# IPM.net
KiCad netlist of a schematic drawn in EasyEDA Pro
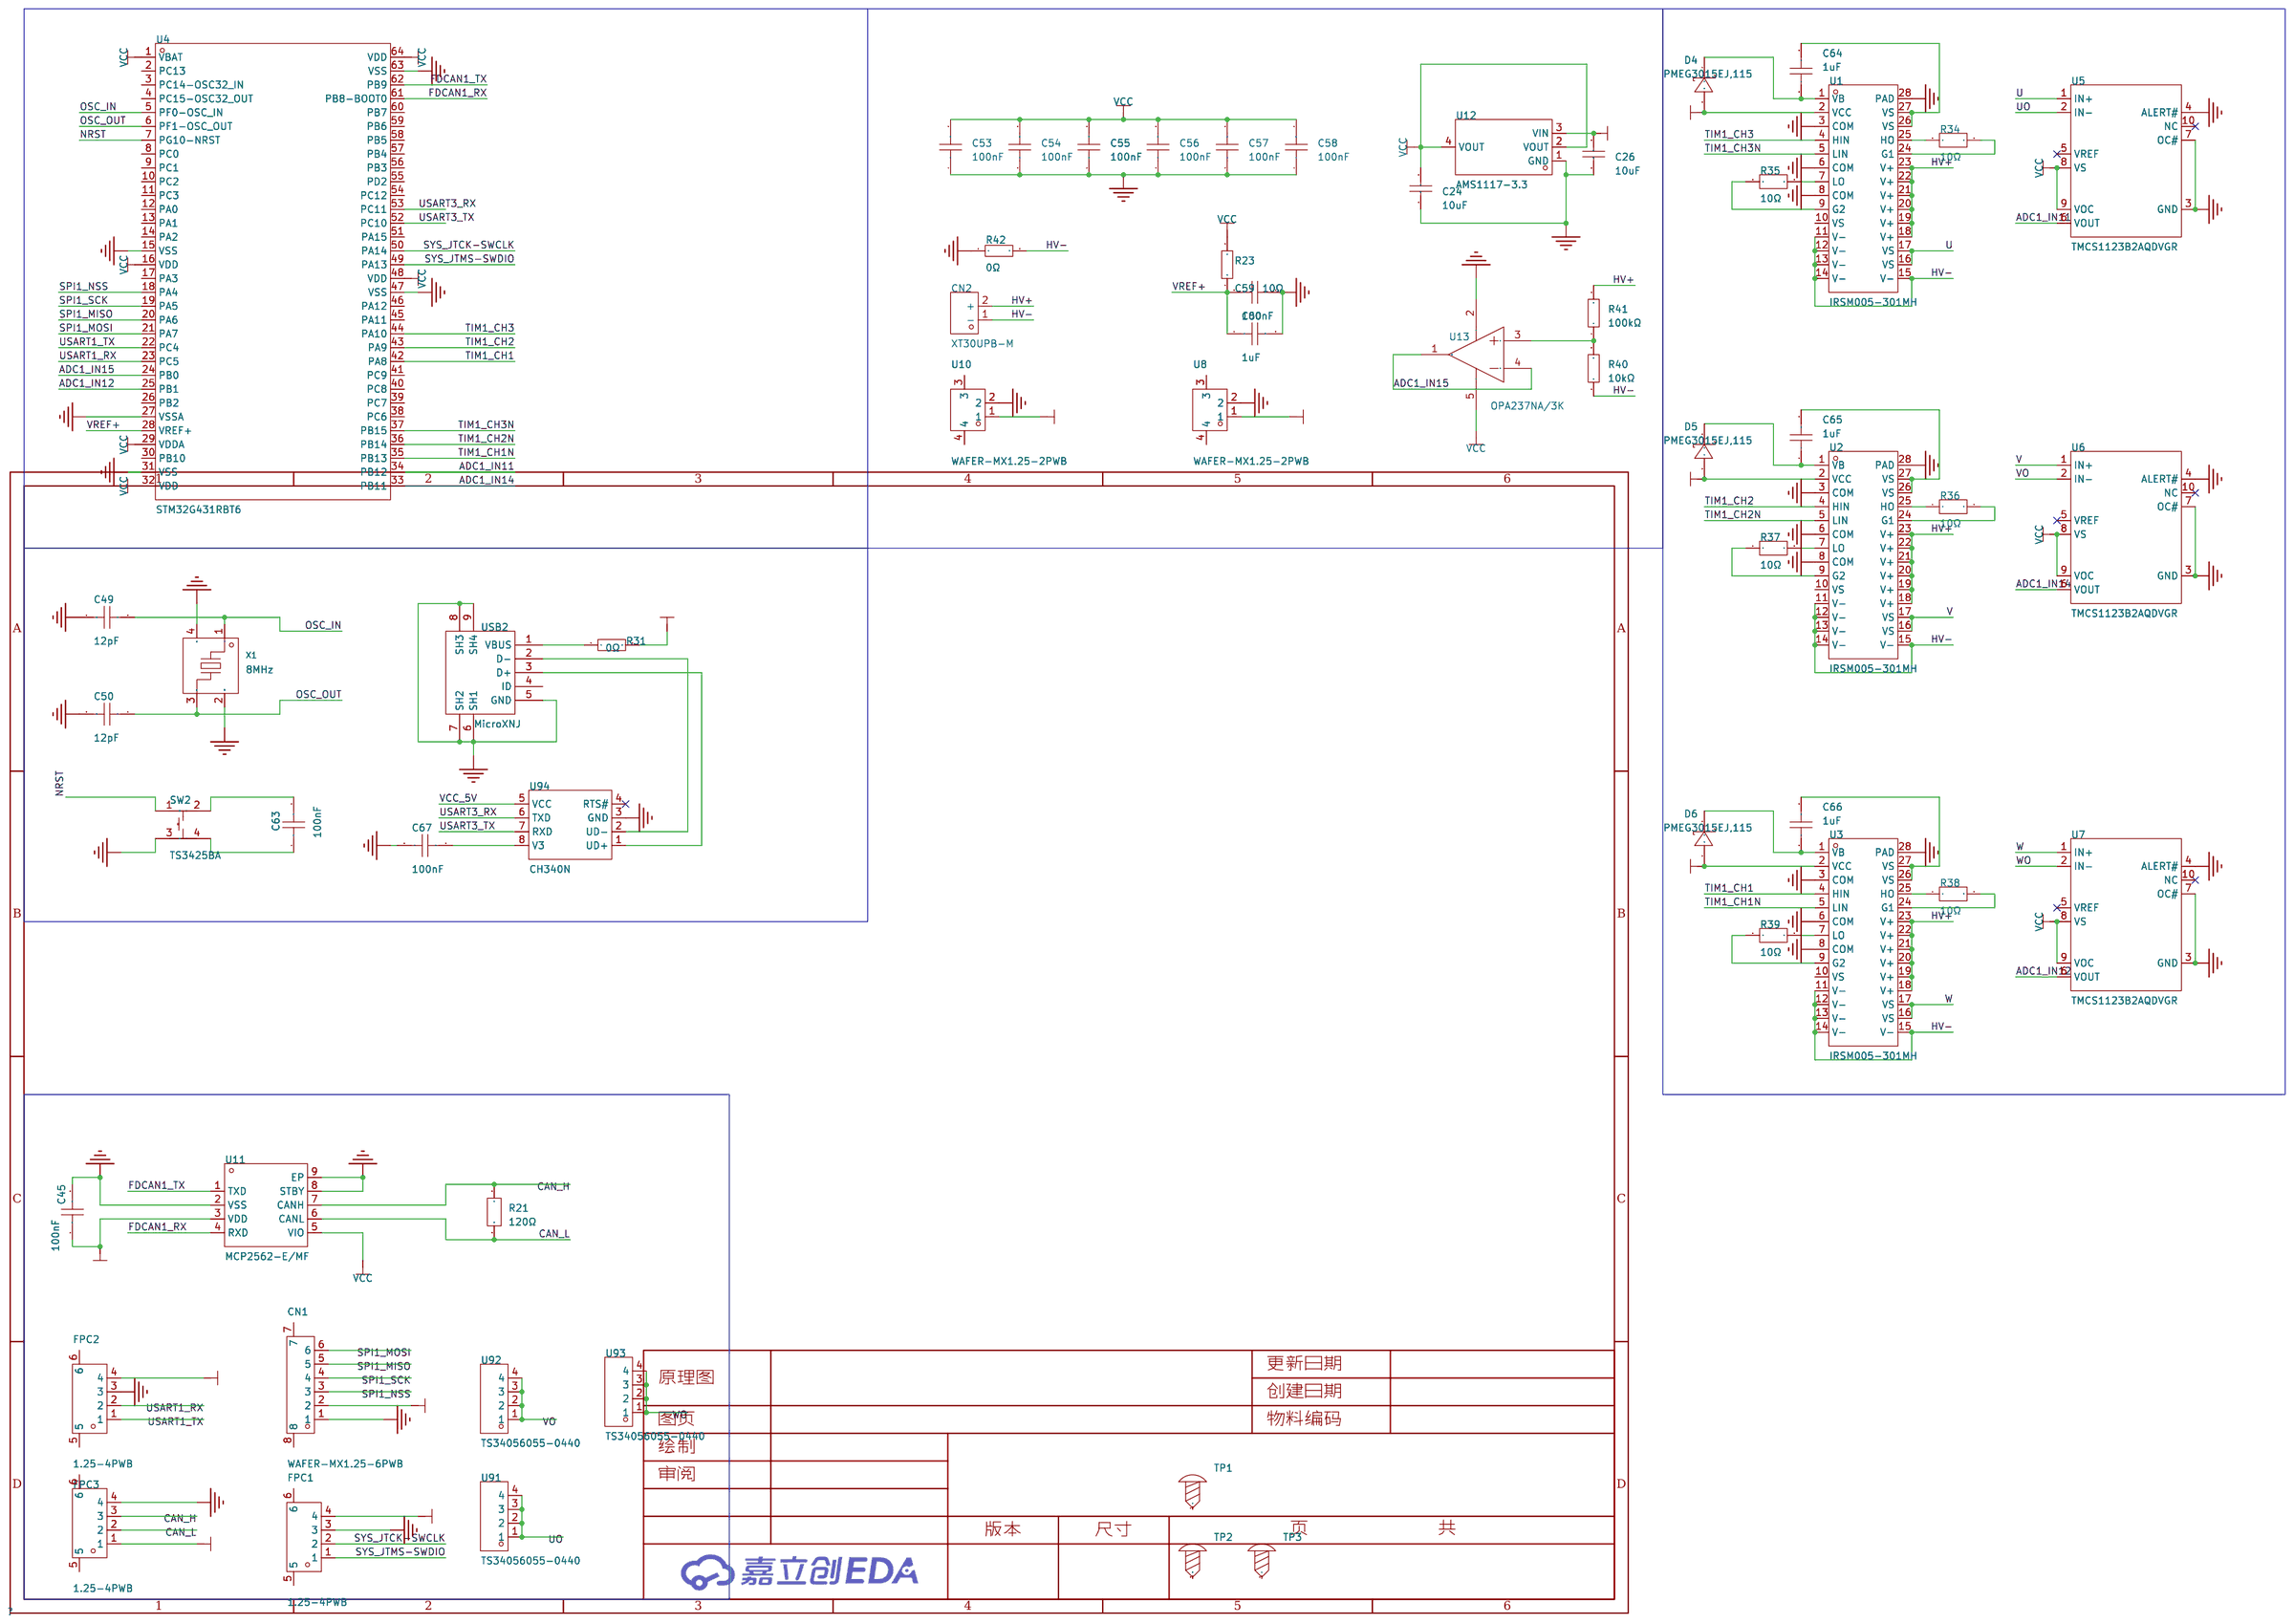
[diagram p0: schematic sheet]

(export (version "E")
  (design (tool "Eeschema 10.0.6"))
  (components
    (comp (ref "C24")
      (value "10uF")
      (footprint "easyedapro:C0603")
      (description "容值:10uF;精度:±10%;额定电压:10V;材质(温度系数):X5R;")
      (fields (field (name "Manufacturer Part") "0603X106K100") (field (name "Manufacturer") "Walsin(华新科)"))
      (libsource (lib "easyedapro") (part "0603X106K100"))
    )
    (comp (ref "C26")
      (value "10uF")
      (footprint "easyedapro:C0603")
      (description "容值:10uF;精度:±10%;额定电压:10V;材质(温度系数):X5R;")
      (fields (field (name "Manufacturer Part") "0603X106K100") (field (name "Manufacturer") "Walsin(华新科)"))
      (libsource (lib "easyedapro") (part "0603X106K100"))
    )
    (comp (ref "C45")
      (value "100nF")
      (footprint "easyedapro:C0603")
      (description "容值:100nF;精度:±10%;额定电压:50V;材质(温度系数):X7R;")
      (fields
        (field (name "Manufacturer Part") "CC0603KRX7R9BB104")
        (field (name "Manufacturer") "YAGEO(国巨)")
      )
      (libsource (lib "easyedapro") (part "CC0603KRX7R9BB104"))
    )
    (comp (ref "C49")
      (value "12pF")
      (footprint "easyedapro:C0603")
      (description "容值:12pF;精度:±1%;额定电压:50V;材质(温度系数):NP0;")
      (fields
        (field (name "Manufacturer Part") "CC0603FRNPO9BN120")
        (field (name "Manufacturer") "YAGEO(国巨)")
      )
      (libsource (lib "easyedapro") (part "CC0603FRNPO9BN120"))
    )
    (comp (ref "C50")
      (value "12pF")
      (footprint "easyedapro:C0603")
      (description "容值:12pF;精度:±1%;额定电压:50V;材质(温度系数):NP0;")
      (fields
        (field (name "Manufacturer Part") "CC0603FRNPO9BN120")
        (field (name "Manufacturer") "YAGEO(国巨)")
      )
      (libsource (lib "easyedapro") (part "CC0603FRNPO9BN120"))
    )
    (comp (ref "C53")
      (value "100nF")
      (footprint "easyedapro:C0603")
      (description "容值:100nF;精度:±10%;额定电压:50V;材质(温度系数):X7R;")
      (fields
        (field (name "Manufacturer Part") "CC0603KRX7R9BB104")
        (field (name "Manufacturer") "YAGEO(国巨)")
      )
      (libsource (lib "easyedapro") (part "CC0603KRX7R9BB104"))
    )
    (comp (ref "C54")
      (value "100nF")
      (footprint "easyedapro:C0603")
      (description "容值:100nF;精度:±10%;额定电压:50V;材质(温度系数):X7R;")
      (fields
        (field (name "Manufacturer Part") "CC0603KRX7R9BB104")
        (field (name "Manufacturer") "YAGEO(国巨)")
      )
      (libsource (lib "easyedapro") (part "CC0603KRX7R9BB104"))
    )
    (comp (ref "C55")
      (value "100nF")
      (footprint "easyedapro:C0603")
      (description "容值:100nF;精度:±10%;额定电压:50V;材质(温度系数):X7R;")
      (fields
        (field (name "Manufacturer Part") "CC0603KRX7R9BB104")
        (field (name "Manufacturer") "YAGEO(国巨)")
      )
      (libsource (lib "easyedapro") (part "CC0603KRX7R9BB104"))
    )
    (comp (ref "C56")
      (value "100nF")
      (footprint "easyedapro:C0603")
      (description "容值:100nF;精度:±10%;额定电压:50V;材质(温度系数):X7R;")
      (fields
        (field (name "Manufacturer Part") "CC0603KRX7R9BB104")
        (field (name "Manufacturer") "YAGEO(国巨)")
      )
      (libsource (lib "easyedapro") (part "CC0603KRX7R9BB104"))
    )
    (comp (ref "C57")
      (value "100nF")
      (footprint "easyedapro:C0603")
      (description "容值:100nF;精度:±10%;额定电压:50V;材质(温度系数):X7R;")
      (fields
        (field (name "Manufacturer Part") "CC0603KRX7R9BB104")
        (field (name "Manufacturer") "YAGEO(国巨)")
      )
      (libsource (lib "easyedapro") (part "CC0603KRX7R9BB104"))
    )
    (comp (ref "C58")
      (value "100nF")
      (footprint "easyedapro:C0603")
      (description "容值:100nF;精度:±10%;额定电压:50V;材质(温度系数):X7R;")
      (fields
        (field (name "Manufacturer Part") "CC0603KRX7R9BB104")
        (field (name "Manufacturer") "YAGEO(国巨)")
      )
      (libsource (lib "easyedapro") (part "CC0603KRX7R9BB104"))
    )
    (comp (ref "C59")
      (value "100nF")
      (footprint "easyedapro:C0603")
      (description "容值:100nF;精度:±10%;额定电压:50V;材质(温度系数):X7R;")
      (fields
        (field (name "Manufacturer Part") "CC0603KRX7R9BB104")
        (field (name "Manufacturer") "YAGEO(国巨)")
      )
      (libsource (lib "easyedapro") (part "CC0603KRX7R9BB104"))
    )
    (comp (ref "C60")
      (value "1uF")
      (footprint "easyedapro:C0603")
      (description "容值:1uF;精度:±5%;额定电压:10V;材质(温度系数):X7R;")
      (fields
        (field (name "Manufacturer Part") "CC0603JRX7R6BB105")
        (field (name "Manufacturer") "YAGEO(国巨)")
      )
      (libsource (lib "easyedapro") (part "CC0603JRX7R6BB105"))
    )
    (comp (ref "C63")
      (value "100nF")
      (footprint "easyedapro:C0603")
      (description "容值:100nF;精度:±10%;额定电压:50V;材质(温度系数):X7R;")
      (fields
        (field (name "Manufacturer Part") "CC0603KRX7R9BB104")
        (field (name "Manufacturer") "YAGEO(国巨)")
      )
      (libsource (lib "easyedapro") (part "CC0603KRX7R9BB104"))
    )
    (comp (ref "C64")
      (value "1uF")
      (footprint "easyedapro:C0603")
      (description "容值:1uF;精度:±10%;额定电压:50V;温度系数:X5R;")
      (fields
        (field (name "Manufacturer Part") "CL10A105KB8NNNC")
        (field (name "Manufacturer") "SAMSUNG(三星)")
      )
      (libsource (lib "easyedapro") (part "CL10A105KB8NNNC"))
    )
    (comp (ref "C65")
      (value "1uF")
      (footprint "easyedapro:C0603")
      (description "容值:1uF;精度:±10%;额定电压:50V;温度系数:X5R;")
      (fields
        (field (name "Manufacturer Part") "CL10A105KB8NNNC")
        (field (name "Manufacturer") "SAMSUNG(三星)")
      )
      (libsource (lib "easyedapro") (part "CL10A105KB8NNNC"))
    )
    (comp (ref "C66")
      (value "1uF")
      (footprint "easyedapro:C0603")
      (description "容值:1uF;精度:±10%;额定电压:50V;温度系数:X5R;")
      (fields
        (field (name "Manufacturer Part") "CL10A105KB8NNNC")
        (field (name "Manufacturer") "SAMSUNG(三星)")
      )
      (libsource (lib "easyedapro") (part "CL10A105KB8NNNC"))
    )
    (comp (ref "C67")
      (value "100nF")
      (footprint "easyedapro:C0603")
      (description "容值:100nF;精度:±10%;额定电压:50V;温度系数:X7R;")
      (fields
        (field (name "Manufacturer Part") "FCC0603B104K500CT")
        (field (name "Manufacturer") "FOJAN(富捷)")
      )
      (libsource (lib "easyedapro") (part "FCC0603B104K500CT"))
    )
    (comp (ref "CN1")
      (value "WAFER-MX1.25-6PWB")
      (footprint "easyedapro:CONN-SMD_6P-P1.25_XUNPU_WAFER-MX1.25-6PWB")
      (fields (field (name "Manufacturer") "XUNPU(讯普)"))
      (libsource (lib "easyedapro") (part "WAFER-MX1.25-6PWB"))
    )
    (comp (ref "CN2")
      (value "XT30UPB-M")
      (footprint "easyedapro:CONN-TH_XT30UPB-M")
      (description "类别:-;类型1:-;")
      (fields (field (name "Manufacturer") "AMASS(艾迈斯)"))
      (libsource (lib "easyedapro") (part "XT30UPB-M"))
    )
    (comp (ref "D4")
      (value "PMEG3015EJ,115")
      (footprint "easyedapro:SOD-323F_L1.7-W1.3-LS2.5-R-RD")
      (description "二极管配置:1个独立式;正向压降(Vf):550mV@1.5A;直流反向耐压(Vr):30V;整流电流:1.5A;")
      (fields (field (name "Manufacturer") "Nexperia(安世)"))
      (libsource (lib "easyedapro") (part "PMEG3015EJ,115"))
    )
    (comp (ref "D5")
      (value "PMEG3015EJ,115")
      (footprint "easyedapro:SOD-323F_L1.7-W1.3-LS2.5-R-RD")
      (description "二极管配置:1个独立式;正向压降(Vf):550mV@1.5A;直流反向耐压(Vr):30V;整流电流:1.5A;")
      (fields (field (name "Manufacturer") "Nexperia(安世)"))
      (libsource (lib "easyedapro") (part "PMEG3015EJ,115"))
    )
    (comp (ref "D6")
      (value "PMEG3015EJ,115")
      (footprint "easyedapro:SOD-323F_L1.7-W1.3-LS2.5-R-RD")
      (description "二极管配置:1个独立式;正向压降(Vf):550mV@1.5A;直流反向耐压(Vr):30V;整流电流:1.5A;")
      (fields (field (name "Manufacturer") "Nexperia(安世)"))
      (libsource (lib "easyedapro") (part "PMEG3015EJ,115"))
    )
    (comp (ref "FPC1")
      (value "1.25-4PWB")
      (footprint "easyedapro:CONN-SMD_1.25-4PWB")
      (fields (field (name "Manufacturer") "DEALON(德艺隆)"))
      (libsource (lib "easyedapro") (part "1.25-4PWB"))
    )
    (comp (ref "FPC2")
      (value "1.25-4PWB")
      (footprint "easyedapro:CONN-SMD_1.25-4PWB")
      (fields (field (name "Manufacturer") "DEALON(德艺隆)"))
      (libsource (lib "easyedapro") (part "1.25-4PWB"))
    )
    (comp (ref "FPC3")
      (value "1.25-4PWB")
      (footprint "easyedapro:CONN-SMD_1.25-4PWB")
      (fields (field (name "Manufacturer") "DEALON(德艺隆)"))
      (libsource (lib "easyedapro") (part "1.25-4PWB"))
    )
    (comp (ref "R21")
      (value "120Ω")
      (footprint "easyedapro:R0603")
      (description "电阻类型:薄膜电阻;阻值:120Ω;精度:±0.1%;功率:100mW;")
      (fields (field (name "Manufacturer Part") "AR03BTCX1200") (field (name "Manufacturer") "Viking(光颉)"))
      (libsource (lib "easyedapro") (part "AR03BTCX1200"))
    )
    (comp (ref "R23")
      (value "10Ω")
      (footprint "easyedapro:R0603")
      (description "电阻类型:厚膜电阻;阻值:10Ω;精度:±1%;功率:100mW;")
      (fields
        (field (name "Manufacturer Part") "0603WAF100JT5E")
        (field (name "Manufacturer") "UNI-ROYAL(厚声)")
      )
      (libsource (lib "easyedapro") (part "0603WAF100JT5E"))
    )
    (comp (ref "R31")
      (value "0Ω")
      (footprint "easyedapro:R0603")
      (description "电阻类型:厚膜电阻;阻值:0Ω;精度:±1%;功率:100mW;最大工作电压:75V;")
      (fields
        (field (name "Manufacturer Part") "0603WAF0000T5E")
        (field (name "Manufacturer") "UNI-ROYAL(厚声)")
      )
      (libsource (lib "easyedapro") (part "0603WAF0000T5E"))
    )
    (comp (ref "R34")
      (value "10Ω")
      (footprint "easyedapro:R0603")
      (description "电阻类型:陶瓷电阻;阻值:10Ω;精度:±0.1%;功率:100mW;温度系数:±25ppm/°C;")
      (fields
        (field (name "Manufacturer Part") "HoARG0603-1/10W-10R-0.1%-TCR25")
        (field (name "Manufacturer") "Milliohm(毫欧)")
      )
      (libsource (lib "easyedapro") (part "HOARG0603-1/10W-10R-0.1%-TCR25"))
    )
    (comp (ref "R35")
      (value "10Ω")
      (footprint "easyedapro:R0603")
      (description "电阻类型:陶瓷电阻;阻值:10Ω;精度:±0.1%;功率:100mW;温度系数:±25ppm/°C;")
      (fields
        (field (name "Manufacturer Part") "HoARG0603-1/10W-10R-0.1%-TCR25")
        (field (name "Manufacturer") "Milliohm(毫欧)")
      )
      (libsource (lib "easyedapro") (part "HOARG0603-1/10W-10R-0.1%-TCR25"))
    )
    (comp (ref "R36")
      (value "10Ω")
      (footprint "easyedapro:R0603")
      (description "电阻类型:陶瓷电阻;阻值:10Ω;精度:±0.1%;功率:100mW;温度系数:±25ppm/°C;")
      (fields
        (field (name "Manufacturer Part") "HoARG0603-1/10W-10R-0.1%-TCR25")
        (field (name "Manufacturer") "Milliohm(毫欧)")
      )
      (libsource (lib "easyedapro") (part "HOARG0603-1/10W-10R-0.1%-TCR25"))
    )
    (comp (ref "R37")
      (value "10Ω")
      (footprint "easyedapro:R0603")
      (description "电阻类型:陶瓷电阻;阻值:10Ω;精度:±0.1%;功率:100mW;温度系数:±25ppm/°C;")
      (fields
        (field (name "Manufacturer Part") "HoARG0603-1/10W-10R-0.1%-TCR25")
        (field (name "Manufacturer") "Milliohm(毫欧)")
      )
      (libsource (lib "easyedapro") (part "HOARG0603-1/10W-10R-0.1%-TCR25"))
    )
    (comp (ref "R38")
      (value "10Ω")
      (footprint "easyedapro:R0603")
      (description "电阻类型:陶瓷电阻;阻值:10Ω;精度:±0.1%;功率:100mW;温度系数:±25ppm/°C;")
      (fields
        (field (name "Manufacturer Part") "HoARG0603-1/10W-10R-0.1%-TCR25")
        (field (name "Manufacturer") "Milliohm(毫欧)")
      )
      (libsource (lib "easyedapro") (part "HOARG0603-1/10W-10R-0.1%-TCR25"))
    )
    (comp (ref "R39")
      (value "10Ω")
      (footprint "easyedapro:R0603")
      (description "电阻类型:陶瓷电阻;阻值:10Ω;精度:±0.1%;功率:100mW;温度系数:±25ppm/°C;")
      (fields
        (field (name "Manufacturer Part") "HoARG0603-1/10W-10R-0.1%-TCR25")
        (field (name "Manufacturer") "Milliohm(毫欧)")
      )
      (libsource (lib "easyedapro") (part "HOARG0603-1/10W-10R-0.1%-TCR25"))
    )
    (comp (ref "R40")
      (value "10kΩ")
      (footprint "easyedapro:R0603")
      (description "电阻类型:薄膜电阻;阻值:10kΩ;精度:±0.1%;功率:100mW;工作电压:75V;温度系数:±25ppm/°C;")
      (fields (field (name "Manufacturer Part") "RT0603BRD0710KL") (field (name "Manufacturer") "YAGEO(国巨)"))
      (libsource (lib "easyedapro") (part "RT0603BRD0710KL"))
    )
    (comp (ref "R41")
      (value "100kΩ")
      (footprint "easyedapro:R0603")
      (description "电阻类型:薄膜电阻;阻值:100kΩ;精度:±0.1%;功率:100mW;最大工作电压:75V;温度系数:±25ppm/°C;")
      (fields (field (name "Manufacturer Part") "RT0603BRD07100KL") (field (name "Manufacturer") "YAGEO(国巨)"))
      (libsource (lib "easyedapro") (part "RT0603BRD07100KL"))
    )
    (comp (ref "R42")
      (value "0Ω")
      (footprint "easyedapro:R0805")
      (description "电阻类型:厚膜电阻;阻值:0Ω;精度:±1%;功率:125mW;工作电压:150V;温度系数:±800ppm/°C;")
      (fields
        (field (name "Manufacturer Part") "0805W8F0000T5E")
        (field (name "Manufacturer") "UNI-ROYAL(厚声)")
      )
      (libsource (lib "easyedapro") (part "0805W8F0000T5E"))
    )
    (comp (ref "SW2")
      (value "TS3425BA")
      (footprint "easyedapro:SW-SMD_4P-L4.2-W3.2-P2.15-LS4.6-1")
      (fields (field (name "Manufacturer") "SHOU HAN(首韩)"))
      (libsource (lib "easyedapro") (part "TS3425BA"))
    )
    (comp (ref "TP1") (value "~") (footprint "easyedapro:M3螺丝") (libsource (lib "easyedapro") (part "螺丝孔")))
    (comp (ref "TP2") (value "~") (footprint "easyedapro:M3螺丝") (libsource (lib "easyedapro") (part "螺丝孔")))
    (comp (ref "TP3") (value "~") (footprint "easyedapro:M3螺丝") (libsource (lib "easyedapro") (part "螺丝孔")))
    (comp (ref "U1")
      (value "IRSM005-301MH")
      (footprint "easyedapro:PQFN-27_IRSM005-800MHTR")
      (description "驱动配置:半桥;负载类型:MOSFET;驱动通道数:2;灌电流(IOL):-;拉电流(IOH):-;工作电压:10V~20V;上升时间(tr):70ns;下降时间(tf):35ns;")
      (fields (field (name "Manufacturer") "Infineon(英飞凌)"))
      (libsource (lib "easyedapro") (part "IRSM005-301MH"))
    )
    (comp (ref "U2")
      (value "IRSM005-301MH")
      (footprint "easyedapro:PQFN-27_IRSM005-800MHTR")
      (description "驱动配置:半桥;负载类型:MOSFET;驱动通道数:2;灌电流(IOL):-;拉电流(IOH):-;工作电压:10V~20V;上升时间(tr):70ns;下降时间(tf):35ns;")
      (fields (field (name "Manufacturer") "Infineon(英飞凌)"))
      (libsource (lib "easyedapro") (part "IRSM005-301MH"))
    )
    (comp (ref "U3")
      (value "IRSM005-301MH")
      (footprint "easyedapro:PQFN-27_IRSM005-800MHTR")
      (description "驱动配置:半桥;负载类型:MOSFET;驱动通道数:2;灌电流(IOL):-;拉电流(IOH):-;工作电压:10V~20V;上升时间(tr):70ns;下降时间(tf):35ns;")
      (fields (field (name "Manufacturer") "Infineon(英飞凌)"))
      (libsource (lib "easyedapro") (part "IRSM005-301MH"))
    )
    (comp (ref "U4")
      (value "STM32G431RBT6")
      (footprint "easyedapro:LQFP-64_L10.0-W10.0-P0.50-LS12.0-BL")
      (description "CPU内核:ARM-M系列;CPU最大主频:170MHz;应用领域:-;")
      (fields (field (name "Manufacturer") "ST(意法半导体)"))
      (libsource (lib "easyedapro") (part "STM32G431RBT6"))
    )
    (comp (ref "U5")
      (value "TMCS1123B2AQDVGR")
      (footprint "easyedapro:SOIC-10_L10.3-W7.5-P1.27-LS10.3-BL")
      (fields (field (name "Manufacturer") "TI(德州仪器)"))
      (libsource (lib "easyedapro") (part "TMCS1123B2AQDVGR"))
    )
    (comp (ref "U6")
      (value "TMCS1123B2AQDVGR")
      (footprint "easyedapro:SOIC-10_L10.3-W7.5-P1.27-LS10.3-BL")
      (fields (field (name "Manufacturer") "TI(德州仪器)"))
      (libsource (lib "easyedapro") (part "TMCS1123B2AQDVGR"))
    )
    (comp (ref "U7")
      (value "TMCS1123B2AQDVGR")
      (footprint "easyedapro:SOIC-10_L10.3-W7.5-P1.27-LS10.3-BL")
      (fields (field (name "Manufacturer") "TI(德州仪器)"))
      (libsource (lib "easyedapro") (part "TMCS1123B2AQDVGR"))
    )
    (comp (ref "U8")
      (value "WAFER-MX1.25-2PWB")
      (footprint "easyedapro:CONN-SMD_2P-P1.25_XUNPU_WAFER-MX1.25-2PWB")
      (fields (field (name "Manufacturer") "XUNPU(讯普)"))
      (libsource (lib "easyedapro") (part "WAFER-MX1.25-2PWB"))
    )
    (comp (ref "U10")
      (value "WAFER-MX1.25-2PWB")
      (footprint "easyedapro:CONN-SMD_2P-P1.25_XUNPU_WAFER-MX1.25-2PWB")
      (fields (field (name "Manufacturer") "XUNPU(讯普)"))
      (libsource (lib "easyedapro") (part "WAFER-MX1.25-2PWB"))
    )
    (comp (ref "U11")
      (value "MCP2562-E/MF")
      (footprint "easyedapro:DFN-8_L3.0-W3.0-P0.65-BL-EP")
      (description "类型:收发器;")
      (fields (field (name "Manufacturer") "MICROCHIP(美国微芯)"))
      (libsource (lib "easyedapro") (part "MCP2562-E/MF"))
    )
    (comp (ref "U12")
      (value "AMS1117-3.3")
      (footprint "easyedapro:SOT-223-3_L6.5-W3.4-P2.30-LS7.0-BR")
      (description "输出类型:固定;输出极性:正;最大输入电压:-;输出电压:3.3V;输出电流:1A;电源纹波抑制比(PSRR):72dB@(120Hz);")
      (fields (field (name "Manufacturer") "AMS"))
      (libsource (lib "easyedapro") (part "AMS1117-3.3"))
    )
    (comp (ref "U13")
      (value "OPA237NA/3K")
      (footprint "easyedapro:SOT-23-5_L3.0-W1.7-P0.95-LS2.8-BR")
      (description "放大器数:单路;增益带宽积(GBP):1.5MHz;输入偏置电流(Ib):10nA;输入失调电压(Vos):250uV;压摆率(SR):0.5V/us;轨到轨:轨到轨输入,轨到轨输出;")
      (fields (field (name "Manufacturer") "TI(德州仪器)"))
      (libsource (lib "easyedapro") (part "OPA237NA/3K"))
    )
    (comp (ref "U91")
      (value "TS34056055-0440")
      (footprint "easyedapro:SMD-4_TS34056055-0440")
      (description "螺孔规格:M3;焊脚数量:4;")
      (fields (field (name "Manufacturer") "XFCN(兴飞)"))
      (libsource (lib "easyedapro") (part "TS34056055-0440"))
    )
    (comp (ref "U92")
      (value "TS34056055-0440")
      (footprint "easyedapro:SMD-4_TS34056055-0440")
      (description "螺孔规格:M3;焊脚数量:4;")
      (fields (field (name "Manufacturer") "XFCN(兴飞)"))
      (libsource (lib "easyedapro") (part "TS34056055-0440"))
    )
    (comp (ref "U93")
      (value "TS34056055-0440")
      (footprint "easyedapro:SMD-4_TS34056055-0440")
      (description "螺孔规格:M3;焊脚数量:4;")
      (fields (field (name "Manufacturer") "XFCN(兴飞)"))
      (libsource (lib "easyedapro") (part "TS34056055-0440"))
    )
    (comp (ref "U94")
      (value "CH340N")
      (footprint "easyedapro:SOP-8_L4.9-W3.9-P1.27-LS6.0-BL")
      (description "应用功能:USB转串口;接口协议:USB 2.0;通道数:1;数据速率:2Mbps;")
      (fields (field (name "Manufacturer") "WCH(南京沁恒)"))
      (libsource (lib "easyedapro") (part "CH340N_C2977777"))
    )
    (comp (ref "USB2")
      (value "MicroXNJ")
      (footprint "easyedapro:MICRO-USB-SMD_MICROXNJ")
      (description "连接器类型:Micro-B;标准:USB 2.0;公母:母;安装方式:卧贴;触点数量:5P;端口数量:1;额定电流 - 电源:1A;工作温度范围:-20°C~+85°C;")
      (fields (field (name "Manufacturer") "SHOU HAN(首韩)"))
      (libsource (lib "easyedapro") (part "MICROXNJ"))
    )
    (comp (ref "X1")
      (value "8MHz")
      (footprint "easyedapro:OSC-SMD_4P-L3.2-W2.5-BL")
      (description "频率:8MHz;频率公差:±10ppm;负载电容:12pF;")
      (fields (field (name "Manufacturer Part") "X32258MOB4SI") (field (name "Manufacturer") "YXC(扬兴晶振)"))
      (libsource (lib "easyedapro") (part "X32258MOB4SI"))
    )
  )
  (nets
    (net (code "1") (name "/ADC1_IN11") (class "Default")
      (node (ref "U4") (pin "34") (pinfunction "PB12_34") (pintype "unspecified"))
      (node (ref "U5") (pin "6") (pinfunction "VOUT_6") (pintype "unspecified"))
    )
    (net (code "2") (name "/ADC1_IN12") (class "Default")
      (node (ref "U4") (pin "25") (pinfunction "PB1_25") (pintype "unspecified"))
      (node (ref "U7") (pin "6") (pinfunction "VOUT_6") (pintype "unspecified"))
    )
    (net (code "3") (name "/ADC1_IN14") (class "Default")
      (node (ref "U4") (pin "33") (pinfunction "PB11_33") (pintype "unspecified"))
      (node (ref "U6") (pin "6") (pinfunction "VOUT_6") (pintype "unspecified"))
    )
    (net (code "4") (name "/ADC1_IN15") (class "Default")
      (node (ref "U13") (pin "1") (pinfunction "OUT_1") (pintype "output"))
      (node (ref "U13") (pin "4") (pinfunction "IN-_4") (pintype "unspecified"))
      (node (ref "U4") (pin "24") (pinfunction "PB0_24") (pintype "unspecified"))
    )
    (net (code "5") (name "/CAN_H") (class "Default")
      (node (ref "FPC3") (pin "3") (pinfunction "3_3") (pintype "unspecified"))
      (node (ref "R21") (pin "2") (pinfunction "2_2") (pintype "input"))
      (node (ref "U11") (pin "7") (pinfunction "CANH_7") (pintype "input"))
    )
    (net (code "6") (name "/CAN_L") (class "Default")
      (node (ref "FPC3") (pin "2") (pinfunction "2_2") (pintype "unspecified"))
      (node (ref "R21") (pin "1") (pinfunction "1_1") (pintype "input"))
      (node (ref "U11") (pin "6") (pinfunction "CANL_6") (pintype "input"))
    )
    (net (code "7") (name "/FDCAN1_RX") (class "Default")
      (node (ref "U11") (pin "4") (pinfunction "RXD_4") (pintype "input"))
      (node (ref "U4") (pin "61") (pinfunction "PB8-BOOT0_61") (pintype "unspecified"))
    )
    (net (code "8") (name "/FDCAN1_TX") (class "Default")
      (node (ref "U11") (pin "1") (pinfunction "TXD_1") (pintype "input"))
      (node (ref "U4") (pin "62") (pinfunction "PB9_62") (pintype "unspecified"))
    )
    (net (code "9") (name "/HV+") (class "Default")
      (node (ref "CN2") (pin "2") (pinfunction "+_2") (pintype "unspecified"))
      (node (ref "R41") (pin "2") (pinfunction "2_2") (pintype "input"))
      (node (ref "U1") (pin "18") (pinfunction "V+_18") (pintype "unspecified"))
      (node (ref "U1") (pin "19") (pinfunction "V+_19") (pintype "unspecified"))
      (node (ref "U1") (pin "20") (pinfunction "V+_20") (pintype "unspecified"))
      (node (ref "U1") (pin "21") (pinfunction "V+_21") (pintype "unspecified"))
      (node (ref "U1") (pin "22") (pinfunction "V+_22") (pintype "unspecified"))
      (node (ref "U1") (pin "23") (pinfunction "V+_23") (pintype "unspecified"))
      (node (ref "U2") (pin "18") (pinfunction "V+_18") (pintype "unspecified"))
      (node (ref "U2") (pin "19") (pinfunction "V+_19") (pintype "unspecified"))
      (node (ref "U2") (pin "20") (pinfunction "V+_20") (pintype "unspecified"))
      (node (ref "U2") (pin "21") (pinfunction "V+_21") (pintype "unspecified"))
      (node (ref "U2") (pin "22") (pinfunction "V+_22") (pintype "unspecified"))
      (node (ref "U2") (pin "23") (pinfunction "V+_23") (pintype "unspecified"))
      (node (ref "U3") (pin "18") (pinfunction "V+_18") (pintype "unspecified"))
      (node (ref "U3") (pin "19") (pinfunction "V+_19") (pintype "unspecified"))
      (node (ref "U3") (pin "20") (pinfunction "V+_20") (pintype "unspecified"))
      (node (ref "U3") (pin "21") (pinfunction "V+_21") (pintype "unspecified"))
      (node (ref "U3") (pin "22") (pinfunction "V+_22") (pintype "unspecified"))
      (node (ref "U3") (pin "23") (pinfunction "V+_23") (pintype "unspecified"))
    )
    (net (code "10") (name "/HV-") (class "Default")
      (node (ref "CN2") (pin "1") (pinfunction "-_1") (pintype "unspecified"))
      (node (ref "R40") (pin "1") (pinfunction "1_1") (pintype "input"))
      (node (ref "R42") (pin "2") (pinfunction "2_2") (pintype "input"))
      (node (ref "U1") (pin "11") (pinfunction "V-_11") (pintype "unspecified"))
      (node (ref "U1") (pin "12") (pinfunction "V-_12") (pintype "unspecified"))
      (node (ref "U1") (pin "13") (pinfunction "V-_13") (pintype "unspecified"))
      (node (ref "U1") (pin "14") (pinfunction "V-_14") (pintype "unspecified"))
      (node (ref "U1") (pin "15") (pinfunction "V-_15") (pintype "unspecified"))
      (node (ref "U2") (pin "11") (pinfunction "V-_11") (pintype "unspecified"))
      (node (ref "U2") (pin "12") (pinfunction "V-_12") (pintype "unspecified"))
      (node (ref "U2") (pin "13") (pinfunction "V-_13") (pintype "unspecified"))
      (node (ref "U2") (pin "14") (pinfunction "V-_14") (pintype "unspecified"))
      (node (ref "U2") (pin "15") (pinfunction "V-_15") (pintype "unspecified"))
      (node (ref "U3") (pin "11") (pinfunction "V-_11") (pintype "unspecified"))
      (node (ref "U3") (pin "12") (pinfunction "V-_12") (pintype "unspecified"))
      (node (ref "U3") (pin "13") (pinfunction "V-_13") (pintype "unspecified"))
      (node (ref "U3") (pin "14") (pinfunction "V-_14") (pintype "unspecified"))
      (node (ref "U3") (pin "15") (pinfunction "V-_15") (pintype "unspecified"))
    )
    (net (code "11") (name "/NRST") (class "Default")
      (node (ref "SW2") (pin "1") (pinfunction "1_1") (pintype "unspecified"))
      (node (ref "U4") (pin "7") (pinfunction "PG10-NRST_7") (pintype "unspecified"))
    )
    (net (code "12") (name "/OSC_IN") (class "Default")
      (node (ref "C49") (pin "1") (pinfunction "1_1") (pintype "input"))
      (node (ref "U4") (pin "5") (pinfunction "PF0-OSC_IN_5") (pintype "unspecified"))
      (node (ref "X1") (pin "1") (pinfunction "1_1") (pintype "input"))
    )
    (net (code "13") (name "/OSC_OUT") (class "Default")
      (node (ref "C50") (pin "1") (pinfunction "1_1") (pintype "input"))
      (node (ref "U4") (pin "6") (pinfunction "PF1-OSC_OUT_6") (pintype "unspecified"))
      (node (ref "X1") (pin "3") (pinfunction "3_3") (pintype "input"))
    )
    (net (code "14") (name "/SPI1_MISO") (class "Default")
      (node (ref "CN1") (pin "5") (pinfunction "5_5") (pintype "unspecified"))
      (node (ref "U4") (pin "20") (pinfunction "PA6_20") (pintype "unspecified"))
    )
    (net (code "15") (name "/SPI1_MOSI") (class "Default")
      (node (ref "CN1") (pin "6") (pinfunction "6_6") (pintype "unspecified"))
      (node (ref "U4") (pin "21") (pinfunction "PA7_21") (pintype "unspecified"))
    )
    (net (code "16") (name "/SPI1_NSS") (class "Default")
      (node (ref "CN1") (pin "3") (pinfunction "3_3") (pintype "unspecified"))
      (node (ref "U4") (pin "18") (pinfunction "PA4_18") (pintype "unspecified"))
    )
    (net (code "17") (name "/SPI1_SCK") (class "Default")
      (node (ref "CN1") (pin "4") (pinfunction "4_4") (pintype "unspecified"))
      (node (ref "U4") (pin "19") (pinfunction "PA5_19") (pintype "unspecified"))
    )
    (net (code "18") (name "/SYS_JTCK-SWCLK") (class "Default")
      (node (ref "FPC1") (pin "2") (pinfunction "2_2") (pintype "unspecified"))
      (node (ref "U4") (pin "50") (pinfunction "PA14_50") (pintype "unspecified"))
    )
    (net (code "19") (name "/SYS_JTMS-SWDIO") (class "Default")
      (node (ref "FPC1") (pin "1") (pinfunction "1_1") (pintype "unspecified"))
      (node (ref "U4") (pin "49") (pinfunction "PA13_49") (pintype "unspecified"))
    )
    (net (code "20") (name "/TIM1_CH1") (class "Default")
      (node (ref "U3") (pin "4") (pinfunction "HIN_4") (pintype "unspecified"))
      (node (ref "U4") (pin "42") (pinfunction "PA8_42") (pintype "unspecified"))
    )
    (net (code "21") (name "/TIM1_CH1N") (class "Default")
      (node (ref "U3") (pin "5") (pinfunction "LIN_5") (pintype "unspecified"))
      (node (ref "U4") (pin "35") (pinfunction "PB13_35") (pintype "unspecified"))
    )
    (net (code "22") (name "/TIM1_CH2") (class "Default")
      (node (ref "U2") (pin "4") (pinfunction "HIN_4") (pintype "unspecified"))
      (node (ref "U4") (pin "43") (pinfunction "PA9_43") (pintype "unspecified"))
    )
    (net (code "23") (name "/TIM1_CH2N") (class "Default")
      (node (ref "U2") (pin "5") (pinfunction "LIN_5") (pintype "unspecified"))
      (node (ref "U4") (pin "36") (pinfunction "PB14_36") (pintype "unspecified"))
    )
    (net (code "24") (name "/TIM1_CH3") (class "Default")
      (node (ref "U1") (pin "4") (pinfunction "HIN_4") (pintype "unspecified"))
      (node (ref "U4") (pin "44") (pinfunction "PA10_44") (pintype "unspecified"))
    )
    (net (code "25") (name "/TIM1_CH3N") (class "Default")
      (node (ref "U1") (pin "5") (pinfunction "LIN_5") (pintype "unspecified"))
      (node (ref "U4") (pin "37") (pinfunction "PB15_37") (pintype "unspecified"))
    )
    (net (code "26") (name "/U") (class "Default")
      (node (ref "U1") (pin "16") (pinfunction "VS_16") (pintype "unspecified"))
      (node (ref "U1") (pin "17") (pinfunction "VS_17") (pintype "unspecified"))
      (node (ref "U5") (pin "1") (pinfunction "IN+_1") (pintype "unspecified"))
    )
    (net (code "27") (name "/UO") (class "Default")
      (node (ref "U5") (pin "2") (pinfunction "IN-_2") (pintype "unspecified"))
      (node (ref "U91") (pin "1") (pinfunction "1_1") (pintype "unspecified"))
      (node (ref "U91") (pin "2") (pinfunction "2_2") (pintype "unspecified"))
      (node (ref "U91") (pin "3") (pinfunction "3_3") (pintype "unspecified"))
      (node (ref "U91") (pin "4") (pinfunction "4_4") (pintype "unspecified"))
    )
    (net (code "28") (name "/USART1_RX") (class "Default")
      (node (ref "FPC2") (pin "2") (pinfunction "2_2") (pintype "unspecified"))
      (node (ref "U4") (pin "23") (pinfunction "PC5_23") (pintype "unspecified"))
    )
    (net (code "29") (name "/USART1_TX") (class "Default")
      (node (ref "FPC2") (pin "1") (pinfunction "1_1") (pintype "unspecified"))
      (node (ref "U4") (pin "22") (pinfunction "PC4_22") (pintype "unspecified"))
    )
    (net (code "30") (name "/USART3_RX") (class "Default")
      (node (ref "U4") (pin "53") (pinfunction "PC11_53") (pintype "unspecified"))
      (node (ref "U94") (pin "6") (pinfunction "TXD_6") (pintype "unspecified"))
    )
    (net (code "31") (name "/USART3_TX") (class "Default")
      (node (ref "U4") (pin "52") (pinfunction "PC10_52") (pintype "unspecified"))
      (node (ref "U94") (pin "7") (pinfunction "RXD_7") (pintype "unspecified"))
    )
    (net (code "32") (name "/V") (class "Default")
      (node (ref "U2") (pin "16") (pinfunction "VS_16") (pintype "unspecified"))
      (node (ref "U2") (pin "17") (pinfunction "VS_17") (pintype "unspecified"))
      (node (ref "U6") (pin "1") (pinfunction "IN+_1") (pintype "unspecified"))
    )
    (net (code "33") (name "/VO") (class "Default")
      (node (ref "U6") (pin "2") (pinfunction "IN-_2") (pintype "unspecified"))
      (node (ref "U92") (pin "1") (pinfunction "1_1") (pintype "unspecified"))
      (node (ref "U92") (pin "2") (pinfunction "2_2") (pintype "unspecified"))
      (node (ref "U92") (pin "3") (pinfunction "3_3") (pintype "unspecified"))
      (node (ref "U92") (pin "4") (pinfunction "4_4") (pintype "unspecified"))
    )
    (net (code "34") (name "/VREF+") (class "Default")
      (node (ref "C59") (pin "2") (pinfunction "2_2") (pintype "input"))
      (node (ref "C60") (pin "1") (pinfunction "1_1") (pintype "input"))
      (node (ref "R23") (pin "1") (pinfunction "1_1") (pintype "input"))
      (node (ref "U4") (pin "28") (pinfunction "VREF+_28") (pintype "unspecified"))
    )
    (net (code "35") (name "/W") (class "Default")
      (node (ref "U3") (pin "16") (pinfunction "VS_16") (pintype "unspecified"))
      (node (ref "U3") (pin "17") (pinfunction "VS_17") (pintype "unspecified"))
      (node (ref "U7") (pin "1") (pinfunction "IN+_1") (pintype "unspecified"))
    )
    (net (code "36") (name "/WO") (class "Default")
      (node (ref "U7") (pin "2") (pinfunction "IN-_2") (pintype "unspecified"))
      (node (ref "U93") (pin "1") (pinfunction "1_1") (pintype "unspecified"))
      (node (ref "U93") (pin "2") (pinfunction "2_2") (pintype "unspecified"))
      (node (ref "U93") (pin "3") (pinfunction "3_3") (pintype "unspecified"))
      (node (ref "U93") (pin "4") (pinfunction "4_4") (pintype "unspecified"))
    )
    (net (code "37") (name "GND") (class "Default")
      (node (ref "C24") (pin "2") (pinfunction "2_2") (pintype "input"))
      (node (ref "C26") (pin "2") (pinfunction "2_2") (pintype "input"))
      (node (ref "C45") (pin "2") (pinfunction "2_2") (pintype "input"))
      (node (ref "C49") (pin "2") (pinfunction "2_2") (pintype "input"))
      (node (ref "C50") (pin "2") (pinfunction "2_2") (pintype "input"))
      (node (ref "C53") (pin "1") (pinfunction "1_1") (pintype "input"))
      (node (ref "C54") (pin "1") (pinfunction "1_1") (pintype "input"))
      (node (ref "C55") (pin "1") (pinfunction "1_1") (pintype "input"))
      (node (ref "C56") (pin "1") (pinfunction "1_1") (pintype "input"))
      (node (ref "C57") (pin "1") (pinfunction "1_1") (pintype "input"))
      (node (ref "C58") (pin "1") (pinfunction "1_1") (pintype "input"))
      (node (ref "C59") (pin "1") (pinfunction "1_1") (pintype "input"))
      (node (ref "C60") (pin "2") (pinfunction "2_2") (pintype "input"))
      (node (ref "C67") (pin "1") (pinfunction "1_1") (pintype "unspecified"))
      (node (ref "CN1") (pin "1") (pinfunction "1_1") (pintype "unspecified"))
      (node (ref "FPC1") (pin "3") (pinfunction "3_3") (pintype "unspecified"))
      (node (ref "FPC2") (pin "3") (pinfunction "3_3") (pintype "unspecified"))
      (node (ref "FPC3") (pin "4") (pinfunction "4_4") (pintype "unspecified"))
      (node (ref "R42") (pin "1") (pinfunction "1_1") (pintype "input"))
      (node (ref "SW2") (pin "3") (pinfunction "3_3") (pintype "unspecified"))
      (node (ref "U1") (pin "28") (pinfunction "PAD_28") (pintype "unspecified"))
      (node (ref "U1") (pin "3") (pinfunction "COM_3") (pintype "unspecified"))
      (node (ref "U1") (pin "6") (pinfunction "COM_6") (pintype "unspecified"))
      (node (ref "U1") (pin "8") (pinfunction "COM_8") (pintype "unspecified"))
      (node (ref "U10") (pin "2") (pinfunction "2_2") (pintype "unspecified"))
      (node (ref "U11") (pin "2") (pinfunction "VSS_2") (pintype "input"))
      (node (ref "U11") (pin "8") (pinfunction "STBY_8") (pintype "input"))
      (node (ref "U11") (pin "9") (pinfunction "EP_9") (pintype "input"))
      (node (ref "U12") (pin "1") (pinfunction "GND_1") (pintype "input"))
      (node (ref "U13") (pin "2") (pinfunction "V-_2") (pintype "unspecified"))
      (node (ref "U2") (pin "28") (pinfunction "PAD_28") (pintype "unspecified"))
      (node (ref "U2") (pin "3") (pinfunction "COM_3") (pintype "unspecified"))
      (node (ref "U2") (pin "6") (pinfunction "COM_6") (pintype "unspecified"))
      (node (ref "U2") (pin "8") (pinfunction "COM_8") (pintype "unspecified"))
      (node (ref "U3") (pin "28") (pinfunction "PAD_28") (pintype "unspecified"))
      (node (ref "U3") (pin "3") (pinfunction "COM_3") (pintype "unspecified"))
      (node (ref "U3") (pin "6") (pinfunction "COM_6") (pintype "unspecified"))
      (node (ref "U3") (pin "8") (pinfunction "COM_8") (pintype "unspecified"))
      (node (ref "U4") (pin "15") (pinfunction "VSS_15") (pintype "unspecified"))
      (node (ref "U4") (pin "27") (pinfunction "VSSA_27") (pintype "unspecified"))
      (node (ref "U4") (pin "31") (pinfunction "VSS_31") (pintype "unspecified"))
      (node (ref "U4") (pin "47") (pinfunction "VSS_47") (pintype "unspecified"))
      (node (ref "U4") (pin "63") (pinfunction "VSS_63") (pintype "unspecified"))
      (node (ref "U5") (pin "3") (pinfunction "GND_3") (pintype "unspecified"))
      (node (ref "U5") (pin "4") (pinfunction "ALERT#_4") (pintype "unspecified"))
      (node (ref "U5") (pin "7") (pinfunction "OC#_7") (pintype "unspecified"))
      (node (ref "U6") (pin "3") (pinfunction "GND_3") (pintype "unspecified"))
      (node (ref "U6") (pin "4") (pinfunction "ALERT#_4") (pintype "unspecified"))
      (node (ref "U6") (pin "7") (pinfunction "OC#_7") (pintype "unspecified"))
      (node (ref "U7") (pin "3") (pinfunction "GND_3") (pintype "unspecified"))
      (node (ref "U7") (pin "4") (pinfunction "ALERT#_4") (pintype "unspecified"))
      (node (ref "U7") (pin "7") (pinfunction "OC#_7") (pintype "unspecified"))
      (node (ref "U8") (pin "2") (pinfunction "2_2") (pintype "unspecified"))
      (node (ref "U94") (pin "3") (pinfunction "GND_3") (pintype "unspecified"))
      (node (ref "USB2") (pin "5") (pinfunction "GND_5") (pintype "unspecified"))
      (node (ref "USB2") (pin "6") (pinfunction "SH1_6") (pintype "unspecified"))
      (node (ref "USB2") (pin "7") (pinfunction "SH2_7") (pintype "unspecified"))
      (node (ref "USB2") (pin "8") (pinfunction "SH3_8") (pintype "unspecified"))
      (node (ref "USB2") (pin "9") (pinfunction "SH4_9") (pintype "unspecified"))
      (node (ref "X1") (pin "2") (pinfunction "GND_2") (pintype "input"))
      (node (ref "X1") (pin "4") (pinfunction "GND_4") (pintype "input"))
    )
    (net (code "38") (name "Net-(C63-Pad1)") (class "Default")
      (node (ref "C63") (pin "1") (pinfunction "1_1") (pintype "input"))
      (node (ref "SW2") (pin "4") (pinfunction "4_4") (pintype "unspecified"))
    )
    (net (code "39") (name "Net-(C63-Pad2)") (class "Default")
      (node (ref "C63") (pin "2") (pinfunction "2_2") (pintype "input"))
      (node (ref "SW2") (pin "2") (pinfunction "2_2") (pintype "unspecified"))
    )
    (net (code "40") (name "Net-(C64-Pad2)") (class "Default")
      (node (ref "C64") (pin "2") (pinfunction "2_2") (pintype "unspecified"))
      (node (ref "U1") (pin "26") (pinfunction "VS_26") (pintype "unspecified"))
      (node (ref "U1") (pin "27") (pinfunction "VS_27") (pintype "unspecified"))
    )
    (net (code "41") (name "Net-(C65-Pad2)") (class "Default")
      (node (ref "C65") (pin "2") (pinfunction "2_2") (pintype "unspecified"))
      (node (ref "U2") (pin "26") (pinfunction "VS_26") (pintype "unspecified"))
      (node (ref "U2") (pin "27") (pinfunction "VS_27") (pintype "unspecified"))
    )
    (net (code "42") (name "Net-(C66-Pad2)") (class "Default")
      (node (ref "C66") (pin "2") (pinfunction "2_2") (pintype "unspecified"))
      (node (ref "U3") (pin "26") (pinfunction "VS_26") (pintype "unspecified"))
      (node (ref "U3") (pin "27") (pinfunction "VS_27") (pintype "unspecified"))
    )
    (net (code "43") (name "Net-(U1-G1)") (class "Default")
      (node (ref "R34") (pin "2") (pinfunction "2_2") (pintype "unspecified"))
      (node (ref "U1") (pin "24") (pinfunction "G1_24") (pintype "unspecified"))
    )
    (net (code "44") (name "Net-(U1-G2)") (class "Default")
      (node (ref "R35") (pin "1") (pinfunction "1_1") (pintype "unspecified"))
      (node (ref "U1") (pin "9") (pinfunction "G2_9") (pintype "unspecified"))
    )
    (net (code "45") (name "Net-(U1-HO)") (class "Default")
      (node (ref "R34") (pin "1") (pinfunction "1_1") (pintype "unspecified"))
      (node (ref "U1") (pin "25") (pinfunction "HO_25") (pintype "unspecified"))
    )
    (net (code "46") (name "Net-(U1-LO)") (class "Default")
      (node (ref "R35") (pin "2") (pinfunction "2_2") (pintype "unspecified"))
      (node (ref "U1") (pin "7") (pinfunction "LO_7") (pintype "unspecified"))
    )
    (net (code "47") (name "Net-(U1-VB)") (class "Default")
      (node (ref "C64") (pin "1") (pinfunction "1_1") (pintype "unspecified"))
      (node (ref "D4") (pin "1") (pinfunction "1_1") (pintype "unspecified"))
      (node (ref "U1") (pin "1") (pinfunction "VB_1") (pintype "unspecified"))
    )
    (net (code "48") (name "Net-(U2-G1)") (class "Default")
      (node (ref "R36") (pin "2") (pinfunction "2_2") (pintype "unspecified"))
      (node (ref "U2") (pin "24") (pinfunction "G1_24") (pintype "unspecified"))
    )
    (net (code "49") (name "Net-(U2-G2)") (class "Default")
      (node (ref "R37") (pin "1") (pinfunction "1_1") (pintype "unspecified"))
      (node (ref "U2") (pin "9") (pinfunction "G2_9") (pintype "unspecified"))
    )
    (net (code "50") (name "Net-(U2-HO)") (class "Default")
      (node (ref "R36") (pin "1") (pinfunction "1_1") (pintype "unspecified"))
      (node (ref "U2") (pin "25") (pinfunction "HO_25") (pintype "unspecified"))
    )
    (net (code "51") (name "Net-(U2-LO)") (class "Default")
      (node (ref "R37") (pin "2") (pinfunction "2_2") (pintype "unspecified"))
      (node (ref "U2") (pin "7") (pinfunction "LO_7") (pintype "unspecified"))
    )
    (net (code "52") (name "Net-(U2-VB)") (class "Default")
      (node (ref "C65") (pin "1") (pinfunction "1_1") (pintype "unspecified"))
      (node (ref "D5") (pin "1") (pinfunction "1_1") (pintype "unspecified"))
      (node (ref "U2") (pin "1") (pinfunction "VB_1") (pintype "unspecified"))
    )
    (net (code "53") (name "Net-(U3-G1)") (class "Default")
      (node (ref "R38") (pin "2") (pinfunction "2_2") (pintype "unspecified"))
      (node (ref "U3") (pin "24") (pinfunction "G1_24") (pintype "unspecified"))
    )
    (net (code "54") (name "Net-(U3-G2)") (class "Default")
      (node (ref "R39") (pin "1") (pinfunction "1_1") (pintype "unspecified"))
      (node (ref "U3") (pin "9") (pinfunction "G2_9") (pintype "unspecified"))
    )
    (net (code "55") (name "Net-(U3-HO)") (class "Default")
      (node (ref "R38") (pin "1") (pinfunction "1_1") (pintype "unspecified"))
      (node (ref "U3") (pin "25") (pinfunction "HO_25") (pintype "unspecified"))
    )
    (net (code "56") (name "Net-(U3-LO)") (class "Default")
      (node (ref "R39") (pin "2") (pinfunction "2_2") (pintype "unspecified"))
      (node (ref "U3") (pin "7") (pinfunction "LO_7") (pintype "unspecified"))
    )
    (net (code "57") (name "Net-(U3-VB)") (class "Default")
      (node (ref "C66") (pin "1") (pinfunction "1_1") (pintype "unspecified"))
      (node (ref "D6") (pin "1") (pinfunction "1_1") (pintype "unspecified"))
      (node (ref "U3") (pin "1") (pinfunction "VB_1") (pintype "unspecified"))
    )
    (net (code "58") (name "Net-(U13-IN+)") (class "Default")
      (node (ref "R40") (pin "2") (pinfunction "2_2") (pintype "input"))
      (node (ref "R41") (pin "1") (pinfunction "1_1") (pintype "input"))
      (node (ref "U13") (pin "3") (pinfunction "IN+_3") (pintype "unspecified"))
    )
    (net (code "59") (name "Net-(U94-UD+)") (class "Default")
      (node (ref "U94") (pin "1") (pinfunction "UD+_1") (pintype "unspecified"))
      (node (ref "USB2") (pin "3") (pinfunction "D+_3") (pintype "unspecified"))
    )
    (net (code "60") (name "Net-(U94-UD-)") (class "Default")
      (node (ref "U94") (pin "2") (pinfunction "UD-_2") (pintype "unspecified"))
      (node (ref "USB2") (pin "2") (pinfunction "D-_2") (pintype "unspecified"))
    )
    (net (code "61") (name "Net-(U94-V3)") (class "Default")
      (node (ref "C67") (pin "2") (pinfunction "2_2") (pintype "unspecified"))
      (node (ref "U94") (pin "8") (pinfunction "V3_8") (pintype "unspecified"))
    )
    (net (code "62") (name "Net-(USB2-VBUS)") (class "Default")
      (node (ref "R31") (pin "1") (pinfunction "1_1") (pintype "input"))
      (node (ref "USB2") (pin "1") (pinfunction "VBUS_1") (pintype "unspecified"))
    )
    (net (code "63") (name "VCC") (class "Default")
      (node (ref "C24") (pin "1") (pinfunction "1_1") (pintype "input"))
      (node (ref "C53") (pin "2") (pinfunction "2_2") (pintype "input"))
      (node (ref "C54") (pin "2") (pinfunction "2_2") (pintype "input"))
      (node (ref "C55") (pin "2") (pinfunction "2_2") (pintype "input"))
      (node (ref "C56") (pin "2") (pinfunction "2_2") (pintype "input"))
      (node (ref "C57") (pin "2") (pinfunction "2_2") (pintype "input"))
      (node (ref "C58") (pin "2") (pinfunction "2_2") (pintype "input"))
      (node (ref "R23") (pin "2") (pinfunction "2_2") (pintype "input"))
      (node (ref "U11") (pin "5") (pinfunction "VIO_5") (pintype "input"))
      (node (ref "U12") (pin "2") (pinfunction "VOUT_2") (pintype "input"))
      (node (ref "U12") (pin "4") (pinfunction "VOUT_4") (pintype "input"))
      (node (ref "U13") (pin "5") (pinfunction "V+_5") (pintype "unspecified"))
      (node (ref "U4") (pin "1") (pinfunction "VBAT_1") (pintype "unspecified"))
      (node (ref "U4") (pin "16") (pinfunction "VDD_16") (pintype "unspecified"))
      (node (ref "U4") (pin "29") (pinfunction "VDDA_29") (pintype "unspecified"))
      (node (ref "U4") (pin "32") (pinfunction "VDD_32") (pintype "unspecified"))
      (node (ref "U4") (pin "48") (pinfunction "VDD_48") (pintype "unspecified"))
      (node (ref "U4") (pin "64") (pinfunction "VDD_64") (pintype "unspecified"))
      (node (ref "U5") (pin "8") (pinfunction "VS_8") (pintype "unspecified"))
      (node (ref "U5") (pin "9") (pinfunction "VOC_9") (pintype "unspecified"))
      (node (ref "U6") (pin "8") (pinfunction "VS_8") (pintype "unspecified"))
      (node (ref "U6") (pin "9") (pinfunction "VOC_9") (pintype "unspecified"))
      (node (ref "U7") (pin "8") (pinfunction "VS_8") (pintype "unspecified"))
      (node (ref "U7") (pin "9") (pinfunction "VOC_9") (pintype "unspecified"))
    )
    (net (code "64") (name "VCC_5V") (class "Default")
      (node (ref "C26") (pin "1") (pinfunction "1_1") (pintype "input"))
      (node (ref "C45") (pin "1") (pinfunction "1_1") (pintype "input"))
      (node (ref "CN1") (pin "2") (pinfunction "2_2") (pintype "unspecified"))
      (node (ref "FPC1") (pin "4") (pinfunction "4_4") (pintype "unspecified"))
      (node (ref "FPC2") (pin "4") (pinfunction "4_4") (pintype "unspecified"))
      (node (ref "FPC3") (pin "1") (pinfunction "1_1") (pintype "unspecified"))
      (node (ref "R31") (pin "2") (pinfunction "2_2") (pintype "input"))
      (node (ref "U11") (pin "3") (pinfunction "VDD_3") (pintype "input"))
      (node (ref "U12") (pin "3") (pinfunction "VIN_3") (pintype "input"))
      (node (ref "U8") (pin "1") (pinfunction "1_1") (pintype "unspecified"))
      (node (ref "U94") (pin "5") (pinfunction "VCC_5") (pintype "unspecified"))
    )
    (net (code "65") (name "VCC_15V") (class "Default")
      (node (ref "D4") (pin "2") (pinfunction "2_2") (pintype "unspecified"))
      (node (ref "D5") (pin "2") (pinfunction "2_2") (pintype "unspecified"))
      (node (ref "D6") (pin "2") (pinfunction "2_2") (pintype "unspecified"))
      (node (ref "U1") (pin "2") (pinfunction "VCC_2") (pintype "unspecified"))
      (node (ref "U10") (pin "1") (pinfunction "1_1") (pintype "unspecified"))
      (node (ref "U2") (pin "2") (pinfunction "VCC_2") (pintype "unspecified"))
      (node (ref "U3") (pin "2") (pinfunction "VCC_2") (pintype "unspecified"))
    )
    (net (code "66") (name "unconnected-(CN1-Pad7)") (class "Default")
      (node (ref "CN1") (pin "7") (pinfunction "7_7") (pintype "unspecified"))
    )
    (net (code "67") (name "unconnected-(CN1-Pad8)") (class "Default")
      (node (ref "CN1") (pin "8") (pinfunction "8_8") (pintype "unspecified"))
    )
    (net (code "68") (name "unconnected-(FPC1-Pad5)") (class "Default")
      (node (ref "FPC1") (pin "5") (pinfunction "5_5") (pintype "unspecified"))
    )
    (net (code "69") (name "unconnected-(FPC1-Pad6)") (class "Default")
      (node (ref "FPC1") (pin "6") (pinfunction "6_6") (pintype "unspecified"))
    )
    (net (code "70") (name "unconnected-(FPC2-Pad5)") (class "Default")
      (node (ref "FPC2") (pin "5") (pinfunction "5_5") (pintype "unspecified"))
    )
    (net (code "71") (name "unconnected-(FPC2-Pad6)") (class "Default")
      (node (ref "FPC2") (pin "6") (pinfunction "6_6") (pintype "unspecified"))
    )
    (net (code "72") (name "unconnected-(FPC3-Pad5)") (class "Default")
      (node (ref "FPC3") (pin "5") (pinfunction "5_5") (pintype "unspecified"))
    )
    (net (code "73") (name "unconnected-(FPC3-Pad6)") (class "Default")
      (node (ref "FPC3") (pin "6") (pinfunction "6_6") (pintype "unspecified"))
    )
    (net (code "74") (name "unconnected-(TP1-Pad1)") (class "Default")
      (node (ref "TP1") (pin "1") (pinfunction "1_1") (pintype "input"))
    )
    (net (code "75") (name "unconnected-(TP2-Pad1)") (class "Default")
      (node (ref "TP2") (pin "1") (pinfunction "1_1") (pintype "input"))
    )
    (net (code "76") (name "unconnected-(TP3-Pad1)") (class "Default")
      (node (ref "TP3") (pin "1") (pinfunction "1_1") (pintype "input"))
    )
    (net (code "77") (name "unconnected-(U1-VS-Pad10)") (class "Default")
      (node (ref "U1") (pin "10") (pinfunction "VS_10") (pintype "unspecified"))
    )
    (net (code "78") (name "unconnected-(U2-VS-Pad10)") (class "Default")
      (node (ref "U2") (pin "10") (pinfunction "VS_10") (pintype "unspecified"))
    )
    (net (code "79") (name "unconnected-(U3-VS-Pad10)") (class "Default")
      (node (ref "U3") (pin "10") (pinfunction "VS_10") (pintype "unspecified"))
    )
    (net (code "80") (name "unconnected-(U4-PA0-Pad12)") (class "Default")
      (node (ref "U4") (pin "12") (pinfunction "PA0_12") (pintype "unspecified"))
    )
    (net (code "81") (name "unconnected-(U4-PA1-Pad13)") (class "Default")
      (node (ref "U4") (pin "13") (pinfunction "PA1_13") (pintype "unspecified"))
    )
    (net (code "82") (name "unconnected-(U4-PA2-Pad14)") (class "Default")
      (node (ref "U4") (pin "14") (pinfunction "PA2_14") (pintype "unspecified"))
    )
    (net (code "83") (name "unconnected-(U4-PA3-Pad17)") (class "Default")
      (node (ref "U4") (pin "17") (pinfunction "PA3_17") (pintype "unspecified"))
    )
    (net (code "84") (name "unconnected-(U4-PA11-Pad45)") (class "Default")
      (node (ref "U4") (pin "45") (pinfunction "PA11_45") (pintype "unspecified"))
    )
    (net (code "85") (name "unconnected-(U4-PA12-Pad46)") (class "Default")
      (node (ref "U4") (pin "46") (pinfunction "PA12_46") (pintype "unspecified"))
    )
    (net (code "86") (name "unconnected-(U4-PA15-Pad51)") (class "Default")
      (node (ref "U4") (pin "51") (pinfunction "PA15_51") (pintype "unspecified"))
    )
    (net (code "87") (name "unconnected-(U4-PB2-Pad26)") (class "Default")
      (node (ref "U4") (pin "26") (pinfunction "PB2_26") (pintype "unspecified"))
    )
    (net (code "88") (name "unconnected-(U4-PB3-Pad56)") (class "Default")
      (node (ref "U4") (pin "56") (pinfunction "PB3_56") (pintype "unspecified"))
    )
    (net (code "89") (name "unconnected-(U4-PB4-Pad57)") (class "Default")
      (node (ref "U4") (pin "57") (pinfunction "PB4_57") (pintype "unspecified"))
    )
    (net (code "90") (name "unconnected-(U4-PB5-Pad58)") (class "Default")
      (node (ref "U4") (pin "58") (pinfunction "PB5_58") (pintype "unspecified"))
    )
    (net (code "91") (name "unconnected-(U4-PB6-Pad59)") (class "Default")
      (node (ref "U4") (pin "59") (pinfunction "PB6_59") (pintype "unspecified"))
    )
    (net (code "92") (name "unconnected-(U4-PB7-Pad60)") (class "Default")
      (node (ref "U4") (pin "60") (pinfunction "PB7_60") (pintype "unspecified"))
    )
    (net (code "93") (name "unconnected-(U4-PB10-Pad30)") (class "Default")
      (node (ref "U4") (pin "30") (pinfunction "PB10_30") (pintype "unspecified"))
    )
    (net (code "94") (name "unconnected-(U4-PC0-Pad8)") (class "Default")
      (node (ref "U4") (pin "8") (pinfunction "PC0_8") (pintype "unspecified"))
    )
    (net (code "95") (name "unconnected-(U4-PC1-Pad9)") (class "Default")
      (node (ref "U4") (pin "9") (pinfunction "PC1_9") (pintype "unspecified"))
    )
    (net (code "96") (name "unconnected-(U4-PC2-Pad10)") (class "Default")
      (node (ref "U4") (pin "10") (pinfunction "PC2_10") (pintype "unspecified"))
    )
    (net (code "97") (name "unconnected-(U4-PC3-Pad11)") (class "Default")
      (node (ref "U4") (pin "11") (pinfunction "PC3_11") (pintype "unspecified"))
    )
    (net (code "98") (name "unconnected-(U4-PC6-Pad38)") (class "Default")
      (node (ref "U4") (pin "38") (pinfunction "PC6_38") (pintype "unspecified"))
    )
    (net (code "99") (name "unconnected-(U4-PC7-Pad39)") (class "Default")
      (node (ref "U4") (pin "39") (pinfunction "PC7_39") (pintype "unspecified"))
    )
    (net (code "100") (name "unconnected-(U4-PC8-Pad40)") (class "Default")
      (node (ref "U4") (pin "40") (pinfunction "PC8_40") (pintype "unspecified"))
    )
    (net (code "101") (name "unconnected-(U4-PC9-Pad41)") (class "Default")
      (node (ref "U4") (pin "41") (pinfunction "PC9_41") (pintype "unspecified"))
    )
    (net (code "102") (name "unconnected-(U4-PC12-Pad54)") (class "Default")
      (node (ref "U4") (pin "54") (pinfunction "PC12_54") (pintype "unspecified"))
    )
    (net (code "103") (name "unconnected-(U4-PC13-Pad2)") (class "Default")
      (node (ref "U4") (pin "2") (pinfunction "PC13_2") (pintype "unspecified"))
    )
    (net (code "104") (name "unconnected-(U4-PC14-OSC32_IN-Pad3)") (class "Default")
      (node (ref "U4") (pin "3") (pinfunction "PC14-OSC32_IN_3") (pintype "unspecified"))
    )
    (net (code "105") (name "unconnected-(U4-PC15-OSC32_OUT-Pad4)") (class "Default")
      (node (ref "U4") (pin "4") (pinfunction "PC15-OSC32_OUT_4") (pintype "unspecified"))
    )
    (net (code "106") (name "unconnected-(U4-PD2-Pad55)") (class "Default")
      (node (ref "U4") (pin "55") (pinfunction "PD2_55") (pintype "unspecified"))
    )
    (net (code "107") (name "unconnected-(U5-NC-Pad10)") (class "Default")
      (node (ref "U5") (pin "10") (pinfunction "NC_10") (pintype "unspecified+no_connect"))
    )
    (net (code "108") (name "unconnected-(U5-VREF-Pad5)") (class "Default")
      (node (ref "U5") (pin "5") (pinfunction "VREF_5") (pintype "unspecified+no_connect"))
    )
    (net (code "109") (name "unconnected-(U6-NC-Pad10)") (class "Default")
      (node (ref "U6") (pin "10") (pinfunction "NC_10") (pintype "unspecified+no_connect"))
    )
    (net (code "110") (name "unconnected-(U6-VREF-Pad5)") (class "Default")
      (node (ref "U6") (pin "5") (pinfunction "VREF_5") (pintype "unspecified+no_connect"))
    )
    (net (code "111") (name "unconnected-(U7-NC-Pad10)") (class "Default")
      (node (ref "U7") (pin "10") (pinfunction "NC_10") (pintype "unspecified+no_connect"))
    )
    (net (code "112") (name "unconnected-(U7-VREF-Pad5)") (class "Default")
      (node (ref "U7") (pin "5") (pinfunction "VREF_5") (pintype "unspecified+no_connect"))
    )
    (net (code "113") (name "unconnected-(U8-Pad3)") (class "Default")
      (node (ref "U8") (pin "3") (pinfunction "3_3") (pintype "unspecified"))
    )
    (net (code "114") (name "unconnected-(U8-Pad4)") (class "Default")
      (node (ref "U8") (pin "4") (pinfunction "4_4") (pintype "unspecified"))
    )
    (net (code "115") (name "unconnected-(U10-Pad3)") (class "Default")
      (node (ref "U10") (pin "3") (pinfunction "3_3") (pintype "unspecified"))
    )
    (net (code "116") (name "unconnected-(U10-Pad4)") (class "Default")
      (node (ref "U10") (pin "4") (pinfunction "4_4") (pintype "unspecified"))
    )
    (net (code "117") (name "unconnected-(U94-RTS#-Pad4)") (class "Default")
      (node (ref "U94") (pin "4") (pinfunction "RTS#_4") (pintype "unspecified+no_connect"))
    )
    (net (code "118") (name "unconnected-(USB2-ID-Pad4)") (class "Default")
      (node (ref "USB2") (pin "4") (pinfunction "ID_4") (pintype "unspecified"))
    )
  )
)
